# StepperMotorBoard.net
KiCad netlist of a schematic drawn in Altium Designer
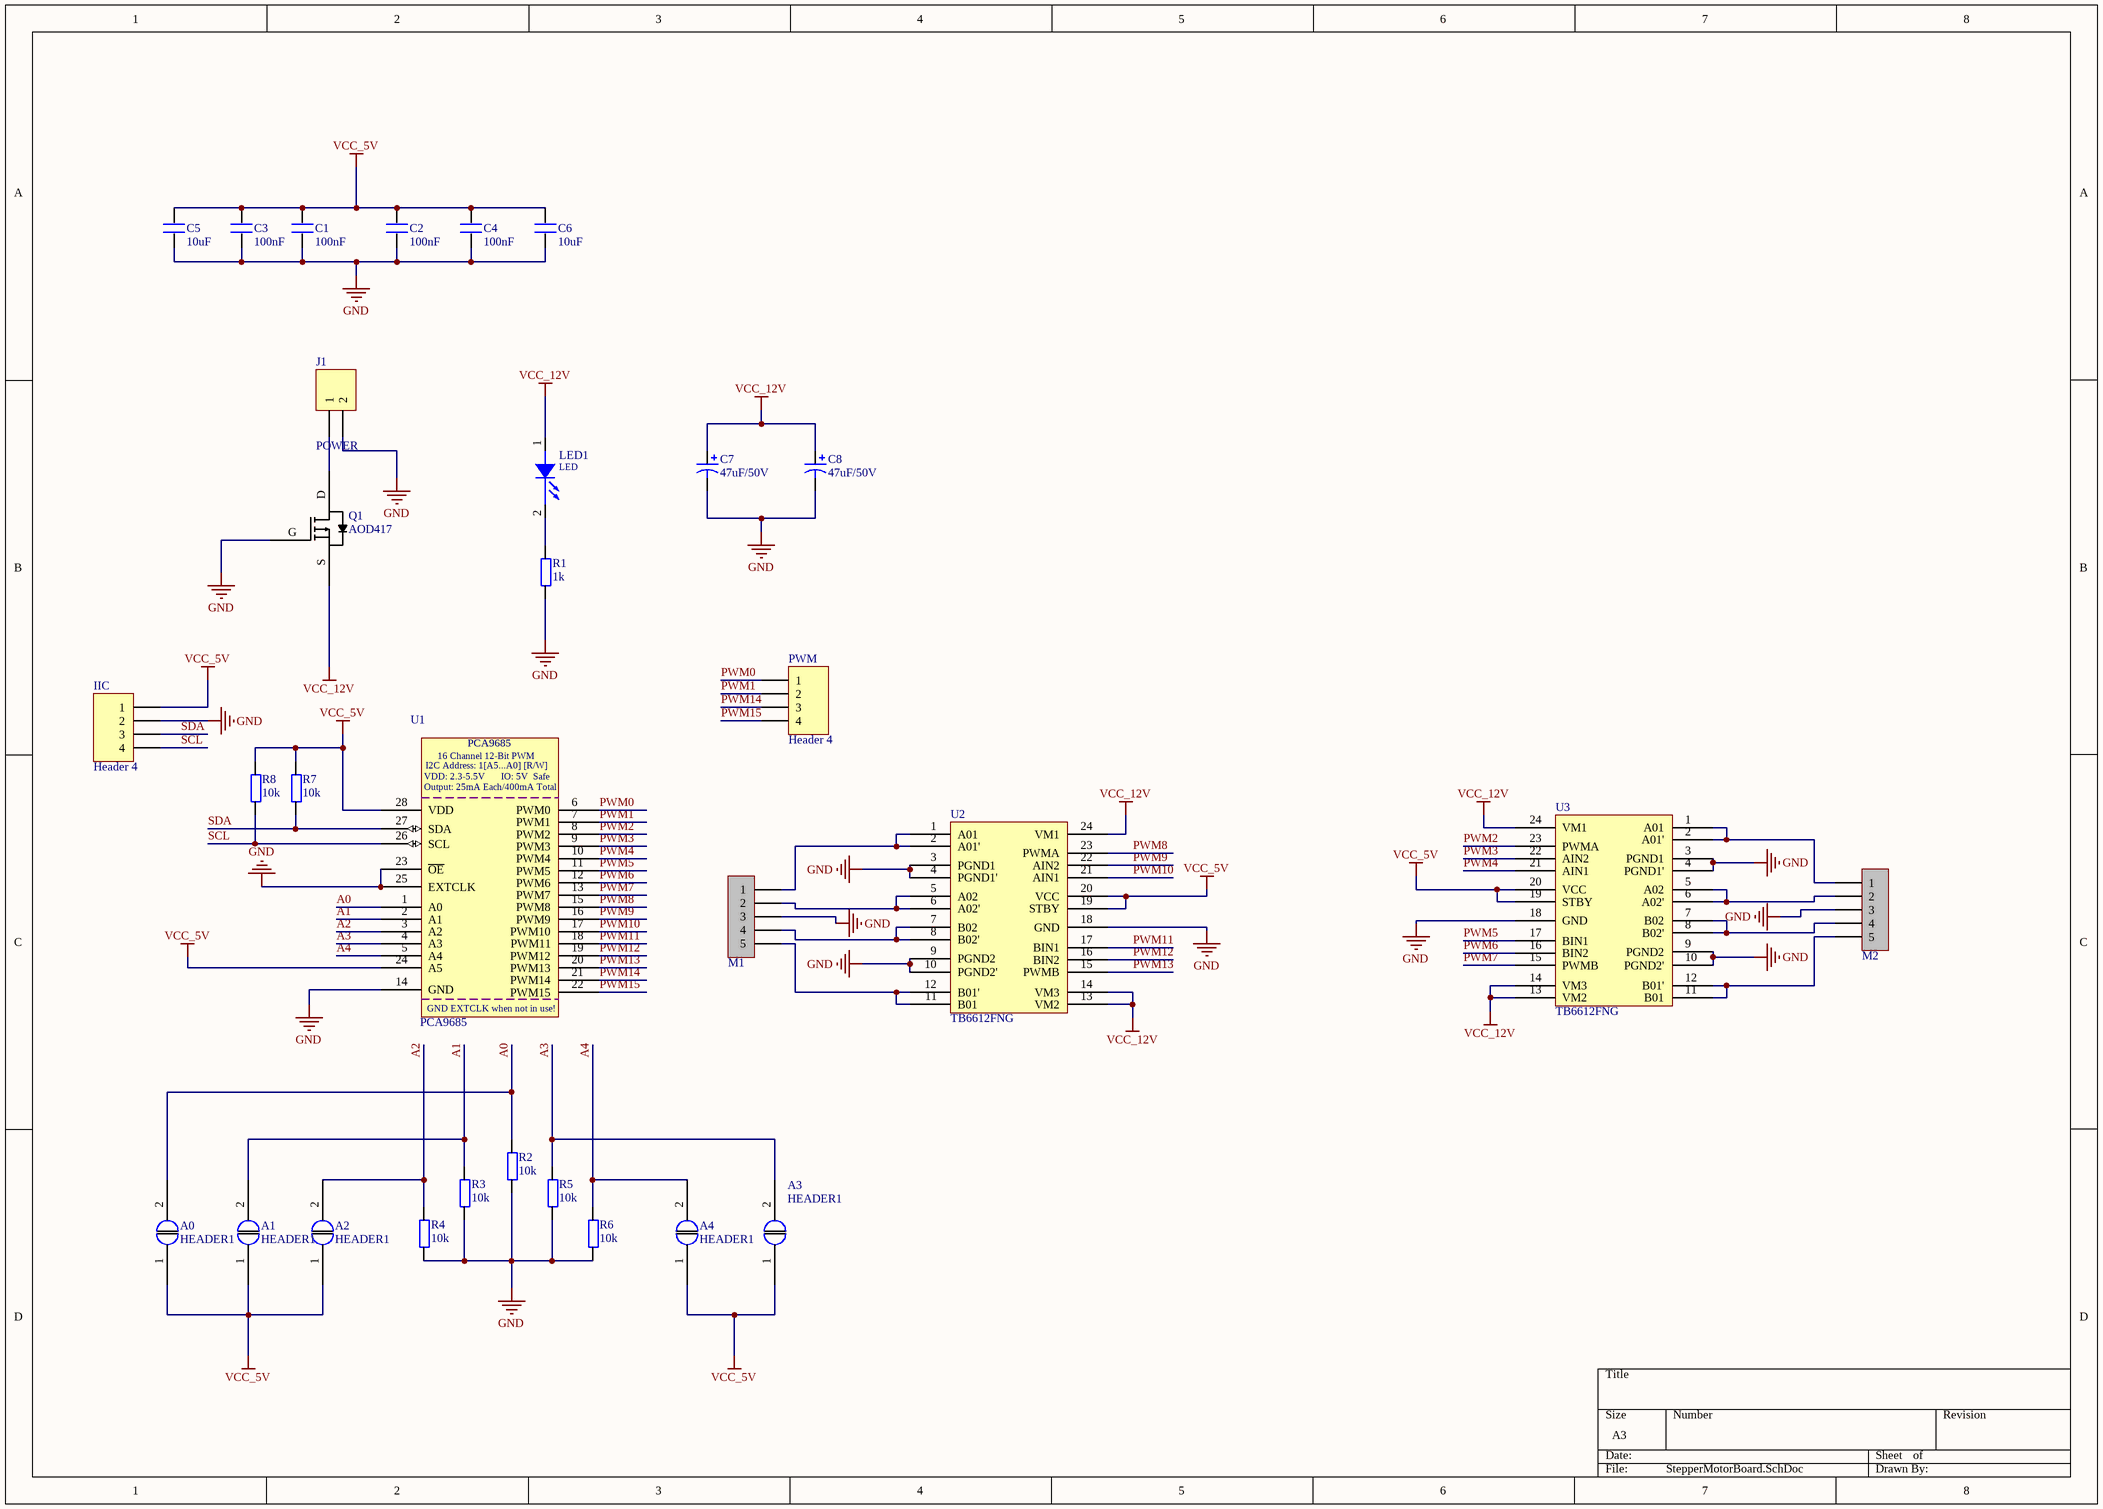
[diagram p0: StepperMotorBoard.SchDoc]

(export (version "E")
  (design (tool "Eeschema 10.0.6"))
  (components
    (comp (ref "A0")
      (value "HEADER1")
      (footprint "HEADER1")
      (libsource (lib "CJ_Component") (part "HEADER1"))
    )
    (comp (ref "A1")
      (value "HEADER1")
      (footprint "HEADER1")
      (libsource (lib "CJ_Component") (part "HEADER1"))
    )
    (comp (ref "A2")
      (value "HEADER1")
      (footprint "HEADER1")
      (libsource (lib "CJ_Component") (part "HEADER1"))
    )
    (comp (ref "A3")
      (value "HEADER1")
      (footprint "HEADER1")
      (libsource (lib "CJ_Component") (part "HEADER1"))
    )
    (comp (ref "A4")
      (value "HEADER1")
      (footprint "HEADER1")
      (libsource (lib "CJ_Component") (part "HEADER1"))
    )
    (comp (ref "C1") (value "100nF") (footprint "0603") (libsource (lib "Control Board") (part "C")))
    (comp (ref "C2") (value "100nF") (footprint "0603") (libsource (lib "Control Board") (part "C")))
    (comp (ref "C3") (value "100nF") (footprint "0603") (libsource (lib "Control Board") (part "C")))
    (comp (ref "C4") (value "100nF") (footprint "0603") (libsource (lib "Control Board") (part "C")))
    (comp (ref "C5") (value "10uF") (footprint "0603") (libsource (lib "Control Board") (part "C")))
    (comp (ref "C6") (value "10uF") (footprint "0603") (libsource (lib "Control Board") (part "C")))
    (comp (ref "C7")
      (value "47uF/50V")
      (footprint "SMDEC-6MM(220MIL)")
      (description "Polarized Capacitor (Radial)")
      (fields (field (name "PART NO.") "VZH101M1CTR-0606"))
      (libsource (lib "Control Board") (part "Cap Pol1"))
    )
    (comp (ref "C8")
      (value "47uF/50V")
      (footprint "SMDEC-6MM(220MIL)")
      (description "Polarized Capacitor (Radial)")
      (fields (field (name "PART NO.") "VZH101M1CTR-0606"))
      (libsource (lib "Control Board") (part "Cap Pol1"))
    )
    (comp (ref "IIC")
      (value "Header 4")
      (footprint "2.54-4")
      (description "Header, 4-Pin")
      (fields (field (name "PUBLISHER") "Altium Limited"))
      (libsource (lib "Control Board") (part "Header 4"))
    )
    (comp (ref "J1")
      (value "POWER")
      (footprint "Terminal block ED655")
      (description "TERMINAL BLOCK 2PIN 25A/300V GREEN 9.52mm PITCH 12-24AWG ROHS")
      (fields (field (name "MANUFACTURER") "On Shore Technology") (field (name "PUBLISHER") "Altium Limited"))
      (libsource (lib "DRV8432") (part "Header 2_1"))
    )
    (comp (ref "LED1") (value "LED") (footprint "SMDLED-0603") (libsource (lib "Control Board") (part "LED")))
    (comp (ref "M1")
      (value "CON5_1")
      (footprint "2.54-5PMR")
      (description "Connector")
      (libsource (lib "") (part "CON5_1_1"))
    )
    (comp (ref "M2")
      (value "CON5_1")
      (footprint "2.54-5PMR")
      (description "Connector")
      (libsource (lib "Control Board") (part "CON5_1"))
    )
    (comp (ref "PWM")
      (value "Header 4")
      (footprint "2.54-4")
      (description "Header, 4-Pin")
      (fields (field (name "PUBLISHER") "Altium Limited"))
      (libsource (lib "") (part "Header 4_1"))
    )
    (comp (ref "Q1")
      (value "AOD417")
      (footprint "TO-252")
      (description "P-Channel Enhancement Mode Field Effect Transistor")
      (libsource (lib "CJ_Component") (part "AOD417"))
    )
    (comp (ref "R1")
      (value "1k")
      (footprint "0603P")
      (description "贴片电阻")
      (libsource (lib "Control Board") (part "R"))
    )
    (comp (ref "R2")
      (value "10k")
      (footprint "0603P")
      (description "贴片电阻")
      (libsource (lib "Control Board") (part "R"))
    )
    (comp (ref "R3")
      (value "10k")
      (footprint "0603P")
      (description "贴片电阻")
      (libsource (lib "Control Board") (part "R"))
    )
    (comp (ref "R4")
      (value "10k")
      (footprint "0603P")
      (description "贴片电阻")
      (libsource (lib "Control Board") (part "R"))
    )
    (comp (ref "R5")
      (value "10k")
      (footprint "0603P")
      (description "贴片电阻")
      (libsource (lib "Control Board") (part "R"))
    )
    (comp (ref "R6")
      (value "10k")
      (footprint "0603P")
      (description "贴片电阻")
      (libsource (lib "Control Board") (part "R"))
    )
    (comp (ref "R7")
      (value "10k")
      (footprint "0603P")
      (description "贴片电阻")
      (libsource (lib "Control Board") (part "R"))
    )
    (comp (ref "R8")
      (value "10k")
      (footprint "0603P")
      (description "贴片电阻")
      (libsource (lib "Control Board") (part "R"))
    )
    (comp (ref "U1")
      (value "PCA9685")
      (footprint "TSOP65P640X110-28N")
      (description "16-channel, 12-bit PWM Fm+ I2C-bus LED controller")
      (libsource (lib "CJ_Component") (part "PCA9685"))
    )
    (comp (ref "U2")
      (value "TB6612FNG")
      (footprint "SSOP65P760X160-24N")
      (description "IC MOTOR DRIVER PAR 24SSOP")
      (libsource (lib "") (part "TB6612FNG_1"))
    )
    (comp (ref "U3")
      (value "TB6612FNG")
      (footprint "SSOP65P760X160-24N")
      (description "IC MOTOR DRIVER PAR 24SSOP")
      (libsource (lib "CJ_Component") (part "TB6612FNG"))
    )
  )
  (nets
    (net (code "1") (name "/A0") (class "Default")
      (node (ref "A0") (pin "2") (pinfunction "2_2") (pintype "passive"))
      (node (ref "R2") (pin "2") (pintype "passive"))
      (node (ref "U1") (pin "1") (pinfunction "A0_1") (pintype "passive"))
    )
    (net (code "2") (name "/A1") (class "Default")
      (node (ref "A1") (pin "2") (pinfunction "2_2") (pintype "passive"))
      (node (ref "R3") (pin "2") (pintype "passive"))
      (node (ref "U1") (pin "2") (pinfunction "A1_2") (pintype "passive"))
    )
    (net (code "3") (name "/A2") (class "Default")
      (node (ref "A2") (pin "2") (pinfunction "2_2") (pintype "passive"))
      (node (ref "R4") (pin "2") (pintype "passive"))
      (node (ref "U1") (pin "3") (pinfunction "A2_3") (pintype "passive"))
    )
    (net (code "4") (name "/A3") (class "Default")
      (node (ref "A3") (pin "2") (pinfunction "2_2") (pintype "passive"))
      (node (ref "R5") (pin "2") (pintype "passive"))
      (node (ref "U1") (pin "4") (pinfunction "A3_4") (pintype "passive"))
    )
    (net (code "5") (name "/A4") (class "Default")
      (node (ref "A4") (pin "2") (pinfunction "2_2") (pintype "passive"))
      (node (ref "R6") (pin "2") (pintype "passive"))
      (node (ref "U1") (pin "5") (pinfunction "A4_5") (pintype "passive"))
    )
    (net (code "6") (name "/PWM0") (class "Default")
      (node (ref "PWM") (pin "1") (pinfunction "1_1") (pintype "passive"))
      (node (ref "U1") (pin "6") (pinfunction "PWM0_6") (pintype "passive"))
    )
    (net (code "7") (name "/PWM1") (class "Default")
      (node (ref "PWM") (pin "2") (pinfunction "2_2") (pintype "passive"))
      (node (ref "U1") (pin "7") (pinfunction "PWM1_7") (pintype "passive"))
    )
    (net (code "8") (name "/PWM2") (class "Default")
      (node (ref "U1") (pin "8") (pinfunction "PWM2_8") (pintype "passive"))
      (node (ref "U3") (pin "23") (pinfunction "PWMA_23") (pintype "passive"))
    )
    (net (code "9") (name "/PWM3") (class "Default")
      (node (ref "U1") (pin "9") (pinfunction "PWM3_9") (pintype "passive"))
      (node (ref "U3") (pin "22") (pinfunction "AIN2_22") (pintype "passive"))
    )
    (net (code "10") (name "/PWM4") (class "Default")
      (node (ref "U1") (pin "10") (pinfunction "PWM4_10") (pintype "passive"))
      (node (ref "U3") (pin "21") (pinfunction "AIN1_21") (pintype "passive"))
    )
    (net (code "11") (name "/PWM5") (class "Default")
      (node (ref "U1") (pin "11") (pinfunction "PWM5_11") (pintype "passive"))
      (node (ref "U3") (pin "17") (pinfunction "BIN1_17") (pintype "passive"))
    )
    (net (code "12") (name "/PWM6") (class "Default")
      (node (ref "U1") (pin "12") (pinfunction "PWM6_12") (pintype "passive"))
      (node (ref "U3") (pin "16") (pinfunction "BIN2_16") (pintype "passive"))
    )
    (net (code "13") (name "/PWM7") (class "Default")
      (node (ref "U1") (pin "13") (pinfunction "PWM7_13") (pintype "passive"))
      (node (ref "U3") (pin "15") (pinfunction "PWMB_15") (pintype "passive"))
    )
    (net (code "14") (name "/PWM8") (class "Default")
      (node (ref "U1") (pin "15") (pinfunction "PWM8_15") (pintype "passive"))
      (node (ref "U2") (pin "23") (pinfunction "PWMA_23") (pintype "passive"))
    )
    (net (code "15") (name "/PWM9") (class "Default")
      (node (ref "U1") (pin "16") (pinfunction "PWM9_16") (pintype "passive"))
      (node (ref "U2") (pin "22") (pinfunction "AIN2_22") (pintype "passive"))
    )
    (net (code "16") (name "/PWM10") (class "Default")
      (node (ref "U1") (pin "17") (pinfunction "PWM10_17") (pintype "passive"))
      (node (ref "U2") (pin "21") (pinfunction "AIN1_21") (pintype "passive"))
    )
    (net (code "17") (name "/PWM11") (class "Default")
      (node (ref "U1") (pin "18") (pinfunction "PWM11_18") (pintype "passive"))
      (node (ref "U2") (pin "17") (pinfunction "BIN1_17") (pintype "passive"))
    )
    (net (code "18") (name "/PWM12") (class "Default")
      (node (ref "U1") (pin "19") (pinfunction "PWM12_19") (pintype "passive"))
      (node (ref "U2") (pin "16") (pinfunction "BIN2_16") (pintype "passive"))
    )
    (net (code "19") (name "/PWM13") (class "Default")
      (node (ref "U1") (pin "20") (pinfunction "PWM13_20") (pintype "passive"))
      (node (ref "U2") (pin "15") (pinfunction "PWMB_15") (pintype "passive"))
    )
    (net (code "20") (name "/PWM14") (class "Default")
      (node (ref "PWM") (pin "3") (pinfunction "3_3") (pintype "passive"))
      (node (ref "U1") (pin "21") (pinfunction "PWM14_21") (pintype "passive"))
    )
    (net (code "21") (name "/PWM15") (class "Default")
      (node (ref "PWM") (pin "4") (pinfunction "4_4") (pintype "passive"))
      (node (ref "U1") (pin "22") (pinfunction "PWM15_22") (pintype "passive"))
    )
    (net (code "22") (name "/SCL") (class "Default")
      (node (ref "IIC") (pin "4") (pinfunction "4_4") (pintype "passive"))
      (node (ref "R8") (pin "1") (pintype "passive"))
      (node (ref "U1") (pin "26") (pinfunction "SCL_26") (pintype "bidirectional"))
    )
    (net (code "23") (name "/SDA") (class "Default")
      (node (ref "IIC") (pin "3") (pinfunction "3_3") (pintype "passive"))
      (node (ref "R7") (pin "1") (pintype "passive"))
      (node (ref "U1") (pin "27") (pinfunction "SDA_27") (pintype "bidirectional"))
    )
    (net (code "24") (name "GND") (class "Default")
      (node (ref "C1") (pin "2") (pintype "passive"))
      (node (ref "C2") (pin "2") (pintype "passive"))
      (node (ref "C3") (pin "2") (pintype "passive"))
      (node (ref "C4") (pin "2") (pintype "passive"))
      (node (ref "C5") (pin "2") (pintype "passive"))
      (node (ref "C6") (pin "2") (pintype "passive"))
      (node (ref "C7") (pin "2") (pinfunction "2_2") (pintype "passive"))
      (node (ref "C8") (pin "2") (pinfunction "2_2") (pintype "passive"))
      (node (ref "IIC") (pin "2") (pinfunction "2_2") (pintype "passive"))
      (node (ref "J1") (pin "2") (pinfunction "2_2") (pintype "passive"))
      (node (ref "M1") (pin "3") (pinfunction "3_3") (pintype "passive"))
      (node (ref "M2") (pin "3") (pinfunction "3_3") (pintype "passive"))
      (node (ref "Q1") (pin "G") (pinfunction "G_G") (pintype "passive"))
      (node (ref "R1") (pin "1") (pintype "passive"))
      (node (ref "R2") (pin "1") (pintype "passive"))
      (node (ref "R3") (pin "1") (pintype "passive"))
      (node (ref "R4") (pin "1") (pintype "passive"))
      (node (ref "R5") (pin "1") (pintype "passive"))
      (node (ref "R6") (pin "1") (pintype "passive"))
      (node (ref "U1") (pin "14") (pinfunction "GND_14") (pintype "power_in"))
      (node (ref "U1") (pin "23") (pinfunction "~{OE}_23") (pintype "passive"))
      (node (ref "U1") (pin "25") (pinfunction "EXTCLK_25") (pintype "passive"))
      (node (ref "U2") (pin "10") (pinfunction "PGND2'_10") (pintype "passive"))
      (node (ref "U2") (pin "18") (pinfunction "GND_18") (pintype "passive"))
      (node (ref "U2") (pin "3") (pinfunction "PGND1_3") (pintype "passive"))
      (node (ref "U2") (pin "4") (pinfunction "PGND1'_4") (pintype "passive"))
      (node (ref "U2") (pin "9") (pinfunction "PGND2_9") (pintype "passive"))
      (node (ref "U3") (pin "10") (pinfunction "PGND2'_10") (pintype "passive"))
      (node (ref "U3") (pin "18") (pinfunction "GND_18") (pintype "passive"))
      (node (ref "U3") (pin "3") (pinfunction "PGND1_3") (pintype "passive"))
      (node (ref "U3") (pin "4") (pinfunction "PGND1'_4") (pintype "passive"))
      (node (ref "U3") (pin "9") (pinfunction "PGND2_9") (pintype "passive"))
    )
    (net (code "25") (name "Net-(J1-Pad1)") (class "Default")
      (node (ref "J1") (pin "1") (pinfunction "1_1") (pintype "passive"))
      (node (ref "Q1") (pin "D") (pinfunction "D_D") (pintype "passive"))
    )
    (net (code "26") (name "Net-(LED1-CATHODE)") (class "Default")
      (node (ref "LED1") (pin "2") (pinfunction "CATHODE_2") (pintype "passive"))
      (node (ref "R1") (pin "2") (pintype "passive"))
    )
    (net (code "27") (name "Net-(U2-A01')") (class "Default")
      (node (ref "M1") (pin "1") (pinfunction "1_1") (pintype "passive"))
      (node (ref "U2") (pin "1") (pinfunction "A01_1") (pintype "passive"))
      (node (ref "U2") (pin "2") (pinfunction "A01'_2") (pintype "passive"))
    )
    (net (code "28") (name "Net-(U2-A02')") (class "Default")
      (node (ref "M1") (pin "2") (pinfunction "2_2") (pintype "passive"))
      (node (ref "U2") (pin "5") (pinfunction "A02_5") (pintype "passive"))
      (node (ref "U2") (pin "6") (pinfunction "A02'_6") (pintype "passive"))
    )
    (net (code "29") (name "Net-(U2-B01')") (class "Default")
      (node (ref "M1") (pin "5") (pinfunction "5_5") (pintype "passive"))
      (node (ref "U2") (pin "11") (pinfunction "B01_11") (pintype "passive"))
      (node (ref "U2") (pin "12") (pinfunction "B01'_12") (pintype "passive"))
    )
    (net (code "30") (name "Net-(U2-B02')") (class "Default")
      (node (ref "M1") (pin "4") (pinfunction "4_4") (pintype "passive"))
      (node (ref "U2") (pin "7") (pinfunction "B02_7") (pintype "passive"))
      (node (ref "U2") (pin "8") (pinfunction "B02'_8") (pintype "passive"))
    )
    (net (code "31") (name "Net-(U3-A01')") (class "Default")
      (node (ref "M2") (pin "1") (pinfunction "1_1") (pintype "passive"))
      (node (ref "U3") (pin "1") (pinfunction "A01_1") (pintype "passive"))
      (node (ref "U3") (pin "2") (pinfunction "A01'_2") (pintype "passive"))
    )
    (net (code "32") (name "Net-(U3-A02')") (class "Default")
      (node (ref "M2") (pin "2") (pinfunction "2_2") (pintype "passive"))
      (node (ref "U3") (pin "5") (pinfunction "A02_5") (pintype "passive"))
      (node (ref "U3") (pin "6") (pinfunction "A02'_6") (pintype "passive"))
    )
    (net (code "33") (name "Net-(U3-B01')") (class "Default")
      (node (ref "M2") (pin "5") (pinfunction "5_5") (pintype "passive"))
      (node (ref "U3") (pin "11") (pinfunction "B01_11") (pintype "passive"))
      (node (ref "U3") (pin "12") (pinfunction "B01'_12") (pintype "passive"))
    )
    (net (code "34") (name "Net-(U3-B02')") (class "Default")
      (node (ref "M2") (pin "4") (pinfunction "4_4") (pintype "passive"))
      (node (ref "U3") (pin "7") (pinfunction "B02_7") (pintype "passive"))
      (node (ref "U3") (pin "8") (pinfunction "B02'_8") (pintype "passive"))
    )
    (net (code "35") (name "VCC_5V") (class "Default")
      (node (ref "A0") (pin "1") (pinfunction "1_1") (pintype "passive"))
      (node (ref "A1") (pin "1") (pinfunction "1_1") (pintype "passive"))
      (node (ref "A2") (pin "1") (pinfunction "1_1") (pintype "passive"))
      (node (ref "A3") (pin "1") (pinfunction "1_1") (pintype "passive"))
      (node (ref "A4") (pin "1") (pinfunction "1_1") (pintype "passive"))
      (node (ref "C1") (pin "1") (pintype "passive"))
      (node (ref "C2") (pin "1") (pintype "passive"))
      (node (ref "C3") (pin "1") (pintype "passive"))
      (node (ref "C4") (pin "1") (pintype "passive"))
      (node (ref "C5") (pin "1") (pintype "passive"))
      (node (ref "C6") (pin "1") (pintype "passive"))
      (node (ref "IIC") (pin "1") (pinfunction "1_1") (pintype "passive"))
      (node (ref "R7") (pin "2") (pintype "passive"))
      (node (ref "R8") (pin "2") (pintype "passive"))
      (node (ref "U1") (pin "24") (pinfunction "A5_24") (pintype "passive"))
      (node (ref "U1") (pin "28") (pinfunction "VDD_28") (pintype "power_in"))
      (node (ref "U2") (pin "19") (pinfunction "STBY_19") (pintype "passive"))
      (node (ref "U2") (pin "20") (pinfunction "VCC_20") (pintype "passive"))
      (node (ref "U3") (pin "19") (pinfunction "STBY_19") (pintype "passive"))
      (node (ref "U3") (pin "20") (pinfunction "VCC_20") (pintype "passive"))
    )
    (net (code "36") (name "VCC_12V") (class "Default")
      (node (ref "C7") (pin "1") (pinfunction "1_1") (pintype "passive"))
      (node (ref "C8") (pin "1") (pinfunction "1_1") (pintype "passive"))
      (node (ref "LED1") (pin "1") (pinfunction "ANODE_1") (pintype "passive"))
      (node (ref "Q1") (pin "S") (pinfunction "S_S") (pintype "passive"))
      (node (ref "U2") (pin "13") (pinfunction "VM2_13") (pintype "passive"))
      (node (ref "U2") (pin "14") (pinfunction "VM3_14") (pintype "passive"))
      (node (ref "U2") (pin "24") (pinfunction "VM1_24") (pintype "passive"))
      (node (ref "U3") (pin "13") (pinfunction "VM2_13") (pintype "passive"))
      (node (ref "U3") (pin "14") (pinfunction "VM3_14") (pintype "passive"))
      (node (ref "U3") (pin "24") (pinfunction "VM1_24") (pintype "passive"))
    )
  )
)
